# PB32Pico_1_x.net
KiCad netlist of a schematic drawn in EAGLE
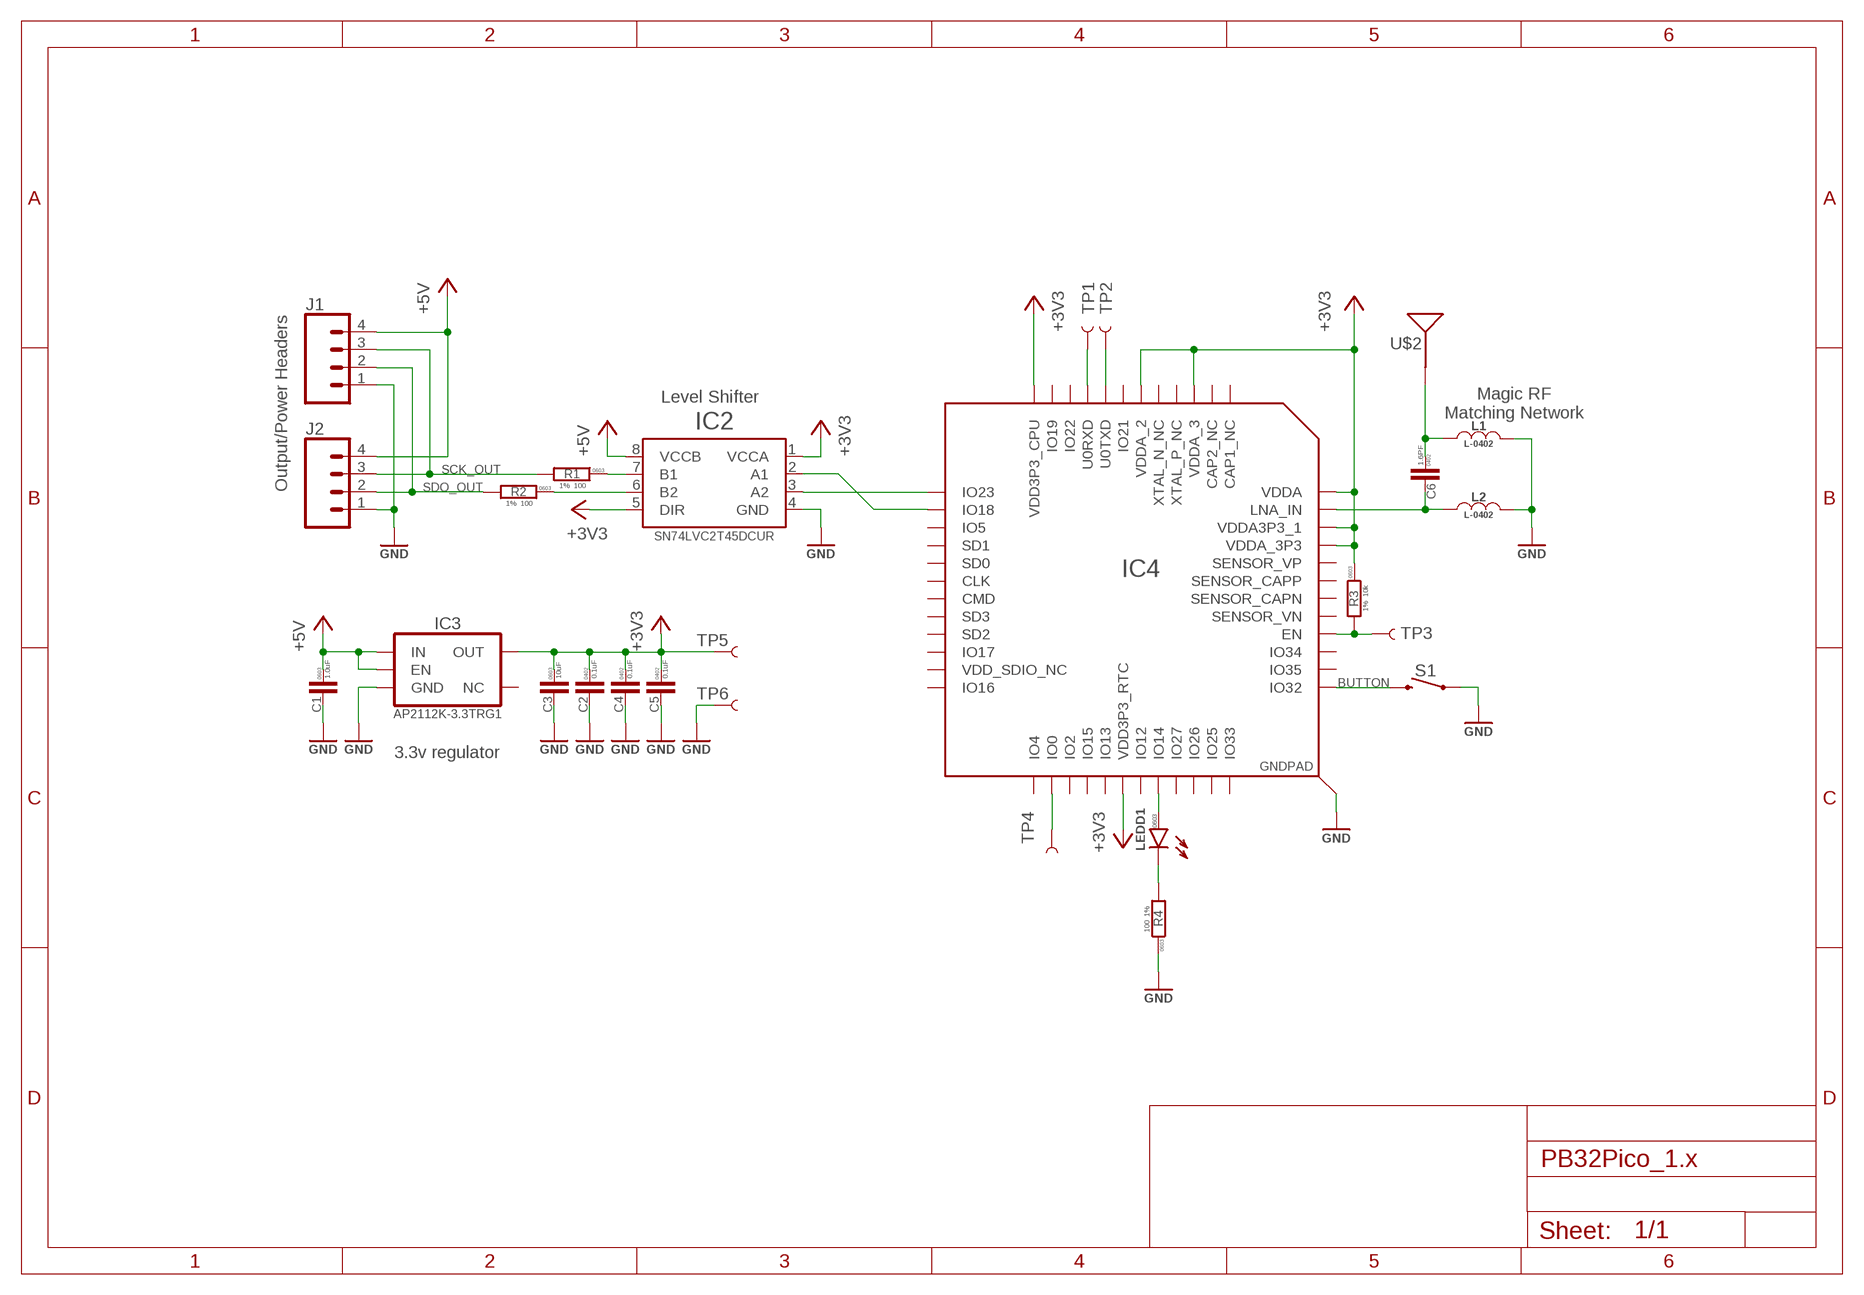
[diagram p0: schematic, sheet 1]

(export (version "E")
  (design (tool "Eeschema 10.0.6"))
  (components
    (comp (ref "C1")
      (value "1.0uF")
      (footprint "eagle-import:C0603")
      (fields (field (name "PACKAGE") "0603"))
      (libsource (lib "eagle-import") (part "C-0603"))
    )
    (comp (ref "C2")
      (value "0.1uF")
      (footprint "eagle-import:C0402")
      (fields (field (name "PACKAGE") "0402"))
      (libsource (lib "eagle-import") (part "C-0402"))
    )
    (comp (ref "C3")
      (value "10uF")
      (footprint "eagle-import:C0603")
      (fields (field (name "PACKAGE") "0603"))
      (libsource (lib "eagle-import") (part "C-0603"))
    )
    (comp (ref "C4")
      (value "0.1uF")
      (footprint "eagle-import:C0402")
      (fields (field (name "PACKAGE") "0402"))
      (libsource (lib "eagle-import") (part "C-0402"))
    )
    (comp (ref "C5")
      (value "0.1uF")
      (footprint "eagle-import:C0402")
      (fields (field (name "PACKAGE") "0402"))
      (libsource (lib "eagle-import") (part "C-0402"))
    )
    (comp (ref "C6")
      (value "1.6PF")
      (footprint "eagle-import:C0402")
      (fields (field (name "PACKAGE") "0402"))
      (libsource (lib "eagle-import") (part "C-0402"))
    )
    (comp (ref "IC2")
      (value "SN74LVC2T45DCUR")
      (footprint "eagle-import:SOP50P310X90-8N")
      (fields (field (name "MANF#") "SN74LVC2T45DCUR"))
      (libsource (lib "eagle-import") (part "SN74LVC2T45DCUR"))
    )
    (comp (ref "IC3")
      (value "3.3V")
      (footprint "eagle-import:SOT23-5")
      (fields (field (name "MANF#") "AP2112K-3.3TRG1"))
      (libsource (lib "eagle-import") (part "V_REG_AP2112K-3.3V"))
    )
    (comp (ref "IC4")
      (value "ESP32-PICO-D4UM-ESP32-PICO-D4")
      (footprint "eagle-import:PICO-D4-QFN48")
      (libsource (lib "eagle-import") (part "ESP32-PICO-D4UM-ESP32-PICO-D4"))
    )
    (comp (ref "J1")
      (value "CONN_041X04_NO_SILK")
      (footprint "eagle-import:1X04_NO_SILK")
      (libsource (lib "eagle-import") (part "CONN_041X04_NO_SILK"))
    )
    (comp (ref "J2")
      (value "CONN_041X04_NO_SILK")
      (footprint "eagle-import:1X04_NO_SILK")
      (libsource (lib "eagle-import") (part "CONN_041X04_NO_SILK"))
    )
    (comp (ref "L1")
      (value "L-0402")
      (footprint "eagle-import:L0402")
      (libsource (lib "eagle-import") (part "L-0402"))
    )
    (comp (ref "L2")
      (value "L-0402")
      (footprint "eagle-import:L0402")
      (libsource (lib "eagle-import") (part "L-0402"))
    )
    (comp (ref "LEDD1")
      (value "LED-0603")
      (footprint "eagle-import:LED0603")
      (fields (field (name "PACKAGE") "0603"))
      (libsource (lib "eagle-import") (part "LED-0603"))
    )
    (comp (ref "R1")
      (value "100")
      (footprint "eagle-import:R0603")
      (fields (field (name "PACKAGE") "0603") (field (name "TOLERANCE") "1%"))
      (libsource (lib "eagle-import") (part "R-0603-1%"))
    )
    (comp (ref "R2")
      (value "100")
      (footprint "eagle-import:R0603")
      (fields (field (name "PACKAGE") "0603") (field (name "TOLERANCE") "1%"))
      (libsource (lib "eagle-import") (part "R-0603-1%"))
    )
    (comp (ref "R3")
      (value "10k")
      (footprint "eagle-import:R0603")
      (fields (field (name "PACKAGE") "0603") (field (name "TOLERANCE") "1%"))
      (libsource (lib "eagle-import") (part "R-0603-1%"))
    )
    (comp (ref "R4")
      (value "100")
      (footprint "eagle-import:R0603")
      (fields (field (name "PACKAGE") "0603") (field (name "TOLERANCE") "1%"))
      (libsource (lib "eagle-import") (part "R-0603-1%"))
    )
    (comp (ref "S1")
      (value "MOMENTARY-SWITCH-SPST-SMD-5.2MM")
      (footprint "eagle-import:TACTILE_SWITCH_SMD_5.2MM")
      (libsource (lib "eagle-import") (part "MOMENTARY-SWITCH-SPST-SMD-5.2MM"))
    )
    (comp (ref "TP1")
      (value "TEST-POINT3X5")
      (footprint "eagle-import:PAD.03X.05")
      (libsource (lib "eagle-import") (part "TEST-POINT3X5"))
    )
    (comp (ref "TP2")
      (value "TEST-POINT3X5")
      (footprint "eagle-import:PAD.03X.05")
      (libsource (lib "eagle-import") (part "TEST-POINT3X5"))
    )
    (comp (ref "TP3")
      (value "TEST-POINT3X5")
      (footprint "eagle-import:PAD.03X.05")
      (libsource (lib "eagle-import") (part "TEST-POINT3X5"))
    )
    (comp (ref "TP4")
      (value "TEST-POINT3X5")
      (footprint "eagle-import:PAD.03X.05")
      (libsource (lib "eagle-import") (part "TEST-POINT3X5"))
    )
    (comp (ref "TP5")
      (value "TEST-POINT3X5")
      (footprint "eagle-import:PAD.03X.05")
      (libsource (lib "eagle-import") (part "TEST-POINT3X5"))
    )
    (comp (ref "TP6")
      (value "TEST-POINT3X5")
      (footprint "eagle-import:PAD.03X.05")
      (libsource (lib "eagle-import") (part "TEST-POINT3X5"))
    )
    (comp (ref "U$2")
      (value "CHIP-ANTENNASHORT")
      (footprint "eagle-import:CHIPANTENNA-1206-SHORT")
      (libsource (lib "eagle-import") (part "CHIP-ANTENNASHORT"))
    )
  )
  (nets
    (net (code "1") (name "+3V3") (class "Default")
      (node (ref "C2") (pin "1") (pinfunction "1_1") (pintype "passive"))
      (node (ref "C3") (pin "1") (pinfunction "1_1") (pintype "passive"))
      (node (ref "C4") (pin "1") (pinfunction "1_1") (pintype "passive"))
      (node (ref "C5") (pin "1") (pinfunction "1_1") (pintype "passive"))
      (node (ref "IC2") (pin "1") (pinfunction "VCCA_1") (pintype "bidirectional"))
      (node (ref "IC2") (pin "5") (pinfunction "DIR_5") (pintype "bidirectional"))
      (node (ref "IC3") (pin "5") (pinfunction "OUT_5") (pintype "passive"))
      (node (ref "IC4") (pin "1") (pinfunction "VDDA_1") (pintype "bidirectional"))
      (node (ref "IC4") (pin "19") (pinfunction "VDD3P3_RTC_19") (pintype "bidirectional"))
      (node (ref "IC4") (pin "3") (pinfunction "VDDA3P3_1_3") (pintype "bidirectional"))
      (node (ref "IC4") (pin "37") (pinfunction "VDD3P3_CPU_37") (pintype "bidirectional"))
      (node (ref "IC4") (pin "4") (pinfunction "VDDA_3P3_4") (pintype "bidirectional"))
      (node (ref "IC4") (pin "43") (pinfunction "VDDA_2_43") (pintype "bidirectional"))
      (node (ref "IC4") (pin "46") (pinfunction "VDDA_3_46") (pintype "bidirectional"))
      (node (ref "R3") (pin "1") (pinfunction "1_1") (pintype "passive"))
      (node (ref "TP5") (pin "P$1") (pinfunction "1_P$1") (pintype "bidirectional"))
    )
    (net (code "2") (name "+5V") (class "Default")
      (node (ref "C1") (pin "1") (pinfunction "1_1") (pintype "passive"))
      (node (ref "IC2") (pin "8") (pinfunction "VCCB_8") (pintype "bidirectional"))
      (node (ref "IC3") (pin "1") (pinfunction "IN_1") (pintype "input"))
      (node (ref "IC3") (pin "3") (pinfunction "EN_3") (pintype "input"))
      (node (ref "J1") (pin "4") (pinfunction "4_4") (pintype "passive"))
      (node (ref "J2") (pin "4") (pinfunction "4_4") (pintype "passive"))
    )
    (net (code "3") (name "/BUTTON") (class "Default")
      (node (ref "IC4") (pin "12") (pinfunction "IO32_12") (pintype "bidirectional"))
      (node (ref "S1") (pin "3") (pinfunction "2_3") (pintype "passive"))
    )
    (net (code "4") (name "/IO12") (class "Default")
      (node (ref "IC4") (pin "18") (pinfunction "IO12_18") (pintype "power_in"))
    )
    (net (code "5") (name "/IO21") (class "Default")
      (node (ref "IC4") (pin "42") (pinfunction "IO21_42") (pintype "power_in"))
    )
    (net (code "6") (name "/SCK_OUT") (class "Default")
      (node (ref "J1") (pin "3") (pinfunction "3_3") (pintype "passive"))
      (node (ref "J2") (pin "3") (pinfunction "3_3") (pintype "passive"))
      (node (ref "R1") (pin "2") (pinfunction "2_2") (pintype "passive"))
    )
    (net (code "7") (name "/SDO_OUT") (class "Default")
      (node (ref "J1") (pin "2") (pinfunction "2_2") (pintype "passive"))
      (node (ref "J2") (pin "2") (pinfunction "2_2") (pintype "passive"))
      (node (ref "R2") (pin "2") (pinfunction "2_2") (pintype "passive"))
    )
    (net (code "8") (name "/SENSOR_CAPN") (class "Default")
      (node (ref "IC4") (pin "7") (pinfunction "SENSOR_CAPN_7") (pintype "power_in"))
    )
    (net (code "9") (name "GND") (class "Default")
      (node (ref "C1") (pin "2") (pinfunction "2_2") (pintype "passive"))
      (node (ref "C2") (pin "2") (pinfunction "2_2") (pintype "passive"))
      (node (ref "C3") (pin "2") (pinfunction "2_2") (pintype "passive"))
      (node (ref "C4") (pin "2") (pinfunction "2_2") (pintype "passive"))
      (node (ref "C5") (pin "2") (pinfunction "2_2") (pintype "passive"))
      (node (ref "IC2") (pin "4") (pinfunction "GND_4") (pintype "bidirectional"))
      (node (ref "IC3") (pin "2") (pinfunction "GND_2") (pintype "input"))
      (node (ref "IC4") (pin "EXP") (pinfunction "GNDPAD_EXP") (pintype "bidirectional"))
      (node (ref "J1") (pin "1") (pinfunction "1_1") (pintype "passive"))
      (node (ref "J2") (pin "1") (pinfunction "1_1") (pintype "passive"))
      (node (ref "L1") (pin "2") (pinfunction "P$2_2") (pintype "bidirectional"))
      (node (ref "L2") (pin "2") (pinfunction "P$2_2") (pintype "bidirectional"))
      (node (ref "R4") (pin "1") (pinfunction "1_1") (pintype "passive"))
      (node (ref "S1") (pin "1") (pinfunction "1_1") (pintype "passive"))
      (node (ref "TP6") (pin "P$1") (pinfunction "1_P$1") (pintype "bidirectional"))
    )
    (net (code "10") (name "Net-(IC2-A1)") (class "Default")
      (node (ref "IC2") (pin "2") (pinfunction "A1_2") (pintype "bidirectional"))
      (node (ref "IC4") (pin "35") (pinfunction "IO18_35") (pintype "bidirectional"))
    )
    (net (code "11") (name "Net-(IC2-A2)") (class "Default")
      (node (ref "IC2") (pin "3") (pinfunction "A2_3") (pintype "bidirectional"))
      (node (ref "IC4") (pin "36") (pinfunction "IO23_36") (pintype "bidirectional"))
    )
    (net (code "12") (name "Net-(IC2-B1)") (class "Default")
      (node (ref "IC2") (pin "7") (pinfunction "B1_7") (pintype "bidirectional"))
      (node (ref "R1") (pin "1") (pinfunction "1_1") (pintype "passive"))
    )
    (net (code "13") (name "Net-(IC2-B2)") (class "Default")
      (node (ref "IC2") (pin "6") (pinfunction "B2_6") (pintype "bidirectional"))
      (node (ref "R2") (pin "1") (pinfunction "1_1") (pintype "passive"))
    )
    (net (code "14") (name "Net-(IC4-EN)") (class "Default")
      (node (ref "IC4") (pin "9") (pinfunction "EN_9") (pintype "bidirectional"))
      (node (ref "R3") (pin "2") (pinfunction "2_2") (pintype "passive"))
      (node (ref "TP3") (pin "P$1") (pinfunction "1_P$1") (pintype "bidirectional"))
    )
    (net (code "15") (name "Net-(IC4-IO0)") (class "Default")
      (node (ref "IC4") (pin "23") (pinfunction "IO0_23") (pintype "bidirectional"))
      (node (ref "TP4") (pin "P$1") (pinfunction "1_P$1") (pintype "bidirectional"))
    )
    (net (code "16") (name "Net-(IC4-IO14)") (class "Default")
      (node (ref "IC4") (pin "17") (pinfunction "IO14_17") (pintype "bidirectional"))
      (node (ref "LEDD1") (pin "A") (pinfunction "A_A") (pintype "bidirectional"))
    )
    (net (code "17") (name "Net-(IC4-LNA_IN)") (class "Default")
      (node (ref "C6") (pin "2") (pinfunction "2_2") (pintype "passive"))
      (node (ref "IC4") (pin "2") (pinfunction "LNA_IN_2") (pintype "bidirectional"))
      (node (ref "L2") (pin "1") (pinfunction "P$1_1") (pintype "bidirectional"))
    )
    (net (code "18") (name "Net-(IC4-U0RXD)") (class "Default")
      (node (ref "IC4") (pin "40") (pinfunction "U0RXD_40") (pintype "bidirectional"))
      (node (ref "TP1") (pin "P$1") (pinfunction "1_P$1") (pintype "bidirectional"))
    )
    (net (code "19") (name "Net-(IC4-U0TXD)") (class "Default")
      (node (ref "IC4") (pin "41") (pinfunction "U0TXD_41") (pintype "bidirectional"))
      (node (ref "TP2") (pin "P$1") (pinfunction "1_P$1") (pintype "bidirectional"))
    )
    (net (code "20") (name "Net-(L1-P$1)") (class "Default")
      (node (ref "C6") (pin "1") (pinfunction "1_1") (pintype "passive"))
      (node (ref "L1") (pin "1") (pinfunction "P$1_1") (pintype "bidirectional"))
      (node (ref "U$2") (pin "P$1") (pinfunction "SIGNAL_P$1") (pintype "bidirectional"))
    )
    (net (code "21") (name "Net-(LEDD1-PadC)") (class "Default")
      (node (ref "LEDD1") (pin "C") (pinfunction "C_C") (pintype "bidirectional"))
      (node (ref "R4") (pin "2") (pinfunction "2_2") (pintype "passive"))
    )
    (net (code "22") (name "unconnected-(IC3-NC-Pad4)") (class "Default")
      (node (ref "IC3") (pin "4") (pinfunction "NC_4") (pintype "input"))
    )
    (net (code "23") (name "unconnected-(IC4-CAP1_NC-Pad48)") (class "Default")
      (node (ref "IC4") (pin "48") (pinfunction "CAP1_NC_48") (pintype "bidirectional"))
    )
    (net (code "24") (name "unconnected-(IC4-CAP2_NC-Pad47)") (class "Default")
      (node (ref "IC4") (pin "47") (pinfunction "CAP2_NC_47") (pintype "bidirectional"))
    )
    (net (code "25") (name "unconnected-(IC4-CLK-Pad31)") (class "Default")
      (node (ref "IC4") (pin "31") (pinfunction "CLK_31") (pintype "bidirectional"))
    )
    (net (code "26") (name "unconnected-(IC4-CMD-Pad30)") (class "Default")
      (node (ref "IC4") (pin "30") (pinfunction "CMD_30") (pintype "bidirectional"))
    )
    (net (code "27") (name "unconnected-(IC4-IO2-Pad22)") (class "Default")
      (node (ref "IC4") (pin "22") (pinfunction "IO2_22") (pintype "bidirectional"))
    )
    (net (code "28") (name "unconnected-(IC4-IO4-Pad24)") (class "Default")
      (node (ref "IC4") (pin "24") (pinfunction "IO4_24") (pintype "bidirectional"))
    )
    (net (code "29") (name "unconnected-(IC4-IO5-Pad34)") (class "Default")
      (node (ref "IC4") (pin "34") (pinfunction "IO5_34") (pintype "bidirectional"))
    )
    (net (code "30") (name "unconnected-(IC4-IO13-Pad20)") (class "Default")
      (node (ref "IC4") (pin "20") (pinfunction "IO13_20") (pintype "bidirectional"))
    )
    (net (code "31") (name "unconnected-(IC4-IO15-Pad21)") (class "Default")
      (node (ref "IC4") (pin "21") (pinfunction "IO15_21") (pintype "bidirectional"))
    )
    (net (code "32") (name "unconnected-(IC4-IO16-Pad25)") (class "Default")
      (node (ref "IC4") (pin "25") (pinfunction "IO16_25") (pintype "bidirectional"))
    )
    (net (code "33") (name "unconnected-(IC4-IO17-Pad27)") (class "Default")
      (node (ref "IC4") (pin "27") (pinfunction "IO17_27") (pintype "bidirectional"))
    )
    (net (code "34") (name "unconnected-(IC4-IO19-Pad38)") (class "Default")
      (node (ref "IC4") (pin "38") (pinfunction "IO19_38") (pintype "bidirectional"))
    )
    (net (code "35") (name "unconnected-(IC4-IO22-Pad39)") (class "Default")
      (node (ref "IC4") (pin "39") (pinfunction "IO22_39") (pintype "bidirectional"))
    )
    (net (code "36") (name "unconnected-(IC4-IO25-Pad14)") (class "Default")
      (node (ref "IC4") (pin "14") (pinfunction "IO25_14") (pintype "bidirectional"))
    )
    (net (code "37") (name "unconnected-(IC4-IO26-Pad15)") (class "Default")
      (node (ref "IC4") (pin "15") (pinfunction "IO26_15") (pintype "bidirectional"))
    )
    (net (code "38") (name "unconnected-(IC4-IO27-Pad16)") (class "Default")
      (node (ref "IC4") (pin "16") (pinfunction "IO27_16") (pintype "bidirectional"))
    )
    (net (code "39") (name "unconnected-(IC4-IO33-Pad13)") (class "Default")
      (node (ref "IC4") (pin "13") (pinfunction "IO33_13") (pintype "bidirectional"))
    )
    (net (code "40") (name "unconnected-(IC4-IO34-Pad10)") (class "Default")
      (node (ref "IC4") (pin "10") (pinfunction "IO34_10") (pintype "bidirectional"))
    )
    (net (code "41") (name "unconnected-(IC4-IO35-Pad11)") (class "Default")
      (node (ref "IC4") (pin "11") (pinfunction "IO35_11") (pintype "bidirectional"))
    )
    (net (code "42") (name "unconnected-(IC4-SD0-Pad32)") (class "Default")
      (node (ref "IC4") (pin "32") (pinfunction "SD0_32") (pintype "bidirectional"))
    )
    (net (code "43") (name "unconnected-(IC4-SD1-Pad33)") (class "Default")
      (node (ref "IC4") (pin "33") (pinfunction "SD1_33") (pintype "bidirectional"))
    )
    (net (code "44") (name "unconnected-(IC4-SD2-Pad28)") (class "Default")
      (node (ref "IC4") (pin "28") (pinfunction "SD2_28") (pintype "bidirectional"))
    )
    (net (code "45") (name "unconnected-(IC4-SD3-Pad29)") (class "Default")
      (node (ref "IC4") (pin "29") (pinfunction "SD3_29") (pintype "bidirectional"))
    )
    (net (code "46") (name "unconnected-(IC4-SENSOR_CAPP-Pad6)") (class "Default")
      (node (ref "IC4") (pin "6") (pinfunction "SENSOR_CAPP_6") (pintype "bidirectional"))
    )
    (net (code "47") (name "unconnected-(IC4-SENSOR_VN-Pad8)") (class "Default")
      (node (ref "IC4") (pin "8") (pinfunction "SENSOR_VN_8") (pintype "bidirectional"))
    )
    (net (code "48") (name "unconnected-(IC4-SENSOR_VP-Pad5)") (class "Default")
      (node (ref "IC4") (pin "5") (pinfunction "SENSOR_VP_5") (pintype "bidirectional"))
    )
    (net (code "49") (name "unconnected-(IC4-VDD_SDIO_NC-Pad26)") (class "Default")
      (node (ref "IC4") (pin "26") (pinfunction "VDD_SDIO_NC_26") (pintype "bidirectional"))
    )
    (net (code "50") (name "unconnected-(IC4-XTAL_N_NC-Pad44)") (class "Default")
      (node (ref "IC4") (pin "44") (pinfunction "XTAL_N_NC_44") (pintype "bidirectional"))
    )
    (net (code "51") (name "unconnected-(IC4-XTAL_P_NC-Pad45)") (class "Default")
      (node (ref "IC4") (pin "45") (pinfunction "XTAL_P_NC_45") (pintype "bidirectional"))
    )
  )
)
